# Sub_B_PCB.net
KiCad netlist of a schematic drawn in Altium Designer
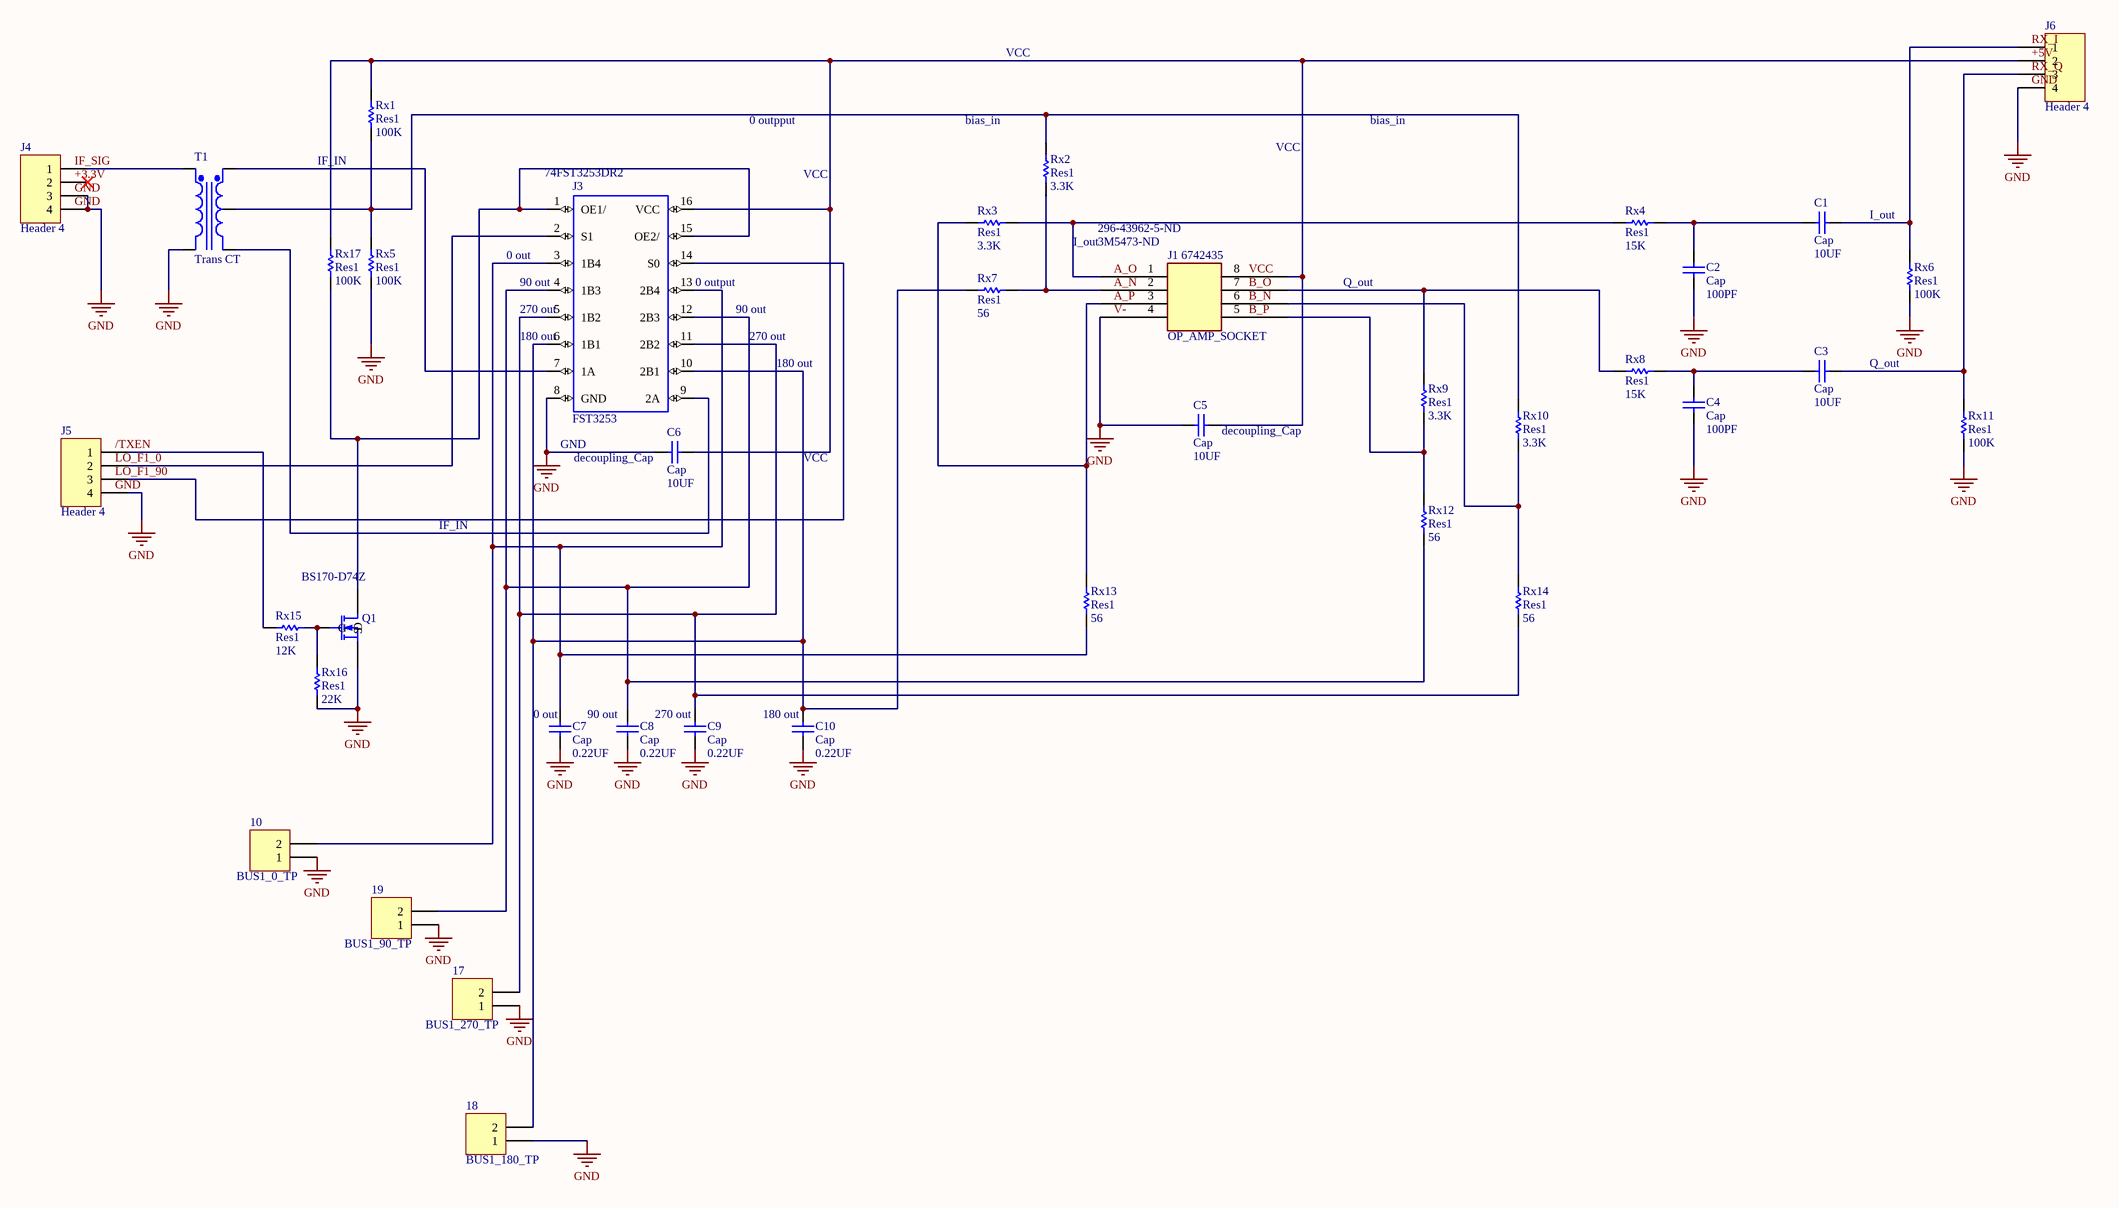
[diagram p0: Sub_B_PCB.SchDoc]

(export (version "E")
  (design (tool "Eeschema 10.0.6"))
  (components
    (comp (ref "10")
      (value "BUS1_0_TP")
      (footprint "HDR1X2")
      (description "Header, 2-Pin")
      (fields (field (name "PUBLISHER") "Altium Limited"))
      (libsource (lib "Miscellaneous Connectors") (part "Header 2"))
    )
    (comp (ref "17")
      (value "BUS1_270_TP")
      (footprint "HDR1X2")
      (description "Header, 2-Pin")
      (fields (field (name "PUBLISHER") "Altium Limited"))
      (libsource (lib "Miscellaneous Connectors") (part "Header 2"))
    )
    (comp (ref "18")
      (value "BUS1_180_TP")
      (footprint "HDR1X2")
      (description "Header, 2-Pin")
      (fields (field (name "PUBLISHER") "Altium Limited"))
      (libsource (lib "Miscellaneous Connectors") (part "Header 2"))
    )
    (comp (ref "19")
      (value "BUS1_90_TP")
      (footprint "HDR1X2")
      (description "Header, 2-Pin")
      (fields (field (name "PUBLISHER") "Altium Limited"))
      (libsource (lib "Miscellaneous Connectors") (part "Header 2"))
    )
    (comp (ref "C1")
      (value "Cap")
      (footprint "1206")
      (description "Capacitor")
      (fields
        (field (name "ALTIUM_VALUE") "10UF")
        (field (name "MANUFACTURER PART NUMBER") "885012108017")
        (field (name "PUBLISHER") "Altium Limited")
      )
      (libsource (lib "ECE295-Capacitors-SMT") (part "CAP CER 10UF 16V X5R 1206"))
    )
    (comp (ref "C2")
      (value "Cap")
      (footprint "RADIAL-0.1")
      (description "Capacitor")
      (fields
        (field (name "ALTIUM_VALUE") "100PF")
        (field (name "MANUFACTURER PART NUMBER") "K101K15C0GF53L2")
        (field (name "PUBLISHER") "Altium Limited")
      )
      (libsource (lib "ECE295-Capacitors-TH") (part "CAP CER 100PF 50V C0G/NP0 RADIAL"))
    )
    (comp (ref "C3")
      (value "Cap")
      (footprint "1206")
      (description "Capacitor")
      (fields
        (field (name "ALTIUM_VALUE") "10UF")
        (field (name "MANUFACTURER PART NUMBER") "885012108017")
        (field (name "PUBLISHER") "Altium Limited")
      )
      (libsource (lib "ECE295-Capacitors-SMT") (part "CAP CER 10UF 16V X5R 1206"))
    )
    (comp (ref "C4")
      (value "Cap")
      (footprint "RADIAL-0.1")
      (description "Capacitor")
      (fields
        (field (name "ALTIUM_VALUE") "100PF")
        (field (name "MANUFACTURER PART NUMBER") "K101K15C0GF53L2")
        (field (name "PUBLISHER") "Altium Limited")
      )
      (libsource (lib "ECE295-Capacitors-TH") (part "CAP CER 100PF 50V C0G/NP0 RADIAL"))
    )
    (comp (ref "C5")
      (value "Cap")
      (footprint "1206")
      (description "Capacitor")
      (fields
        (field (name "ALTIUM_VALUE") "10UF")
        (field (name "MANUFACTURER PART NUMBER") "885012108017")
        (field (name "PUBLISHER") "Altium Limited")
      )
      (libsource (lib "ECE295-Capacitors-SMT") (part "CAP CER 10UF 16V X5R 1206"))
    )
    (comp (ref "C6")
      (value "Cap")
      (footprint "1206")
      (description "Capacitor")
      (fields
        (field (name "ALTIUM_VALUE") "10UF")
        (field (name "MANUFACTURER PART NUMBER") "885012108017")
        (field (name "PUBLISHER") "Altium Limited")
      )
      (libsource (lib "ECE295-Capacitors-SMT") (part "CAP CER 10UF 16V X5R 1206"))
    )
    (comp (ref "C7")
      (value "Cap")
      (footprint "RADIAL-0.1")
      (description "Capacitor")
      (fields
        (field (name "ALTIUM_VALUE") "0.22UF")
        (field (name "MANUFACTURER PART NUMBER") "C320C224M5U5TA")
        (field (name "PUBLISHER") "Altium Limited")
      )
      (libsource (lib "ECE295-Capacitors-TH") (part "CAP CER 0.22UF 50V Z5U RADIAL"))
    )
    (comp (ref "C8")
      (value "Cap")
      (footprint "RADIAL-0.1")
      (description "Capacitor")
      (fields
        (field (name "ALTIUM_VALUE") "0.22UF")
        (field (name "MANUFACTURER PART NUMBER") "C320C224M5U5TA")
        (field (name "PUBLISHER") "Altium Limited")
      )
      (libsource (lib "ECE295-Capacitors-TH") (part "CAP CER 0.22UF 50V Z5U RADIAL"))
    )
    (comp (ref "C9")
      (value "Cap")
      (footprint "RADIAL-0.1")
      (description "Capacitor")
      (fields
        (field (name "ALTIUM_VALUE") "0.22UF")
        (field (name "MANUFACTURER PART NUMBER") "C320C224M5U5TA")
        (field (name "PUBLISHER") "Altium Limited")
      )
      (libsource (lib "ECE295-Capacitors-TH") (part "CAP CER 0.22UF 50V Z5U RADIAL"))
    )
    (comp (ref "C10")
      (value "Cap")
      (footprint "RADIAL-0.1")
      (description "Capacitor")
      (fields
        (field (name "ALTIUM_VALUE") "0.22UF")
        (field (name "MANUFACTURER PART NUMBER") "C320C224M5U5TA")
        (field (name "PUBLISHER") "Altium Limited")
      )
      (libsource (lib "ECE295-Capacitors-TH") (part "CAP CER 0.22UF 50V Z5U RADIAL"))
    )
    (comp (ref "J1")
      (value "OP_AMP_SOCKET")
      (footprint "TE_1-2199298-2")
      (description "8 _2 x 4_ Pos DIP, 0.3 _7.62mm_ Row Spacing Socket Tin Through Hole")
      (fields
        (field (name "MF") "TE Connectivity")
        (field (name "MP") "1-2199298-2")
        (field (name "SUPPLIER PART NUMBER 2") "6742435")
        (field (name "SUPPLIER PART NUMBER 3") "3M5473-ND")
        (field (name "SUPPLIER PART NUMBER 4") "296-43962-5-ND")
      )
      (libsource (lib "1-2199298-2") (part "1-2199298-2"))
    )
    (comp (ref "J3")
      (value "FST3253")
      (footprint "SOIC127P600X175-16N")
      (description "Multiplekser/demultiplekser 2 x 4:1 16-TSSOP")
      (fields (field (name "MF") "ON Semiconductor") (field (name "SUPPLIER PART NUMBER 1") "74FST3253DR2"))
      (libsource (lib "FST3253") (part "FST3253"))
    )
    (comp (ref "J4")
      (value "Header 4")
      (footprint "HDR1X4")
      (description "Header, 4-Pin")
      (fields (field (name "PUBLISHER") "Altium Limited"))
      (libsource (lib "") (part "Header 4_1"))
    )
    (comp (ref "J5")
      (value "Header 4")
      (footprint "HDR1X4")
      (description "Header, 4-Pin")
      (fields (field (name "PUBLISHER") "Altium Limited"))
      (libsource (lib "") (part "Header 4_1"))
    )
    (comp (ref "J6")
      (value "Header 4")
      (footprint "HDR1X4")
      (description "Header, 4-Pin")
      (fields (field (name "PUBLISHER") "Altium Limited"))
      (libsource (lib "Miscellaneous Connectors") (part "Header 4"))
    )
    (comp (ref "Q1")
      (value "MOSFET-N")
      (footprint "E3")
      (description "N-Channel MOSFET")
      (fields
        (field (name "SUPPLIER PART NUMBER 1") "BS170-D74Z")
        (field (name "PUBLISHER") "Altium Limited")
      )
      (libsource (lib "Miscellaneous Devices") (part "MOSFET-N"))
    )
    (comp (ref "Rx1")
      (value "Res1")
      (footprint "AXIAL-0.1-RES")
      (description "Resistor")
      (fields
        (field (name "ALTIUM_VALUE") "100K")
        (field (name "MANUFACTURER PART NUMBER") "CFR-25JB-52-100K")
        (field (name "TOLERANCE") "0.05")
        (field (name "PUBLISHER") "Altium Limited")
      )
      (libsource (lib "ECE295-Resistors-TH") (part "RES 100K OHM 5% 1/4W AXIAL"))
    )
    (comp (ref "Rx2")
      (value "Res1")
      (footprint "AXIAL-0.1-RES")
      (description "Resistor")
      (fields
        (field (name "ALTIUM_VALUE") "3.3K")
        (field (name "MANUFACTURER PART NUMBER") "CFR-25JB-52-3K3")
        (field (name "TOLERANCE") "0.05")
        (field (name "PUBLISHER") "Altium Limited")
      )
      (libsource (lib "ECE295-Resistors-TH") (part "RES 3.3K OHM 5% 1/4W AXIAL"))
    )
    (comp (ref "Rx3")
      (value "Res1")
      (footprint "AXIAL-0.1-RES")
      (description "Resistor")
      (fields
        (field (name "ALTIUM_VALUE") "3.3K")
        (field (name "MANUFACTURER PART NUMBER") "CFR-25JB-52-3K3")
        (field (name "TOLERANCE") "0.05")
        (field (name "PUBLISHER") "Altium Limited")
      )
      (libsource (lib "ECE295-Resistors-TH") (part "RES 3.3K OHM 5% 1/4W AXIAL"))
    )
    (comp (ref "Rx4")
      (value "Res1")
      (footprint "AXIAL-0.1-RES")
      (description "Resistor")
      (fields
        (field (name "ALTIUM_VALUE") "15K")
        (field (name "MANUFACTURER PART NUMBER") "CFR-25JB-52-15K")
        (field (name "TOLERANCE") "0.05")
        (field (name "PUBLISHER") "Altium Limited")
      )
      (libsource (lib "ECE295-Resistors-TH") (part "RES 15K OHM 5% 1/4W AXIAL"))
    )
    (comp (ref "Rx5")
      (value "Res1")
      (footprint "AXIAL-0.1-RES")
      (description "Resistor")
      (fields
        (field (name "ALTIUM_VALUE") "100K")
        (field (name "MANUFACTURER PART NUMBER") "CFR-25JB-52-100K")
        (field (name "TOLERANCE") "0.05")
        (field (name "PUBLISHER") "Altium Limited")
      )
      (libsource (lib "ECE295-Resistors-TH") (part "RES 100K OHM 5% 1/4W AXIAL"))
    )
    (comp (ref "Rx6")
      (value "Res1")
      (footprint "AXIAL-0.1-RES")
      (description "Resistor")
      (fields
        (field (name "ALTIUM_VALUE") "100K")
        (field (name "MANUFACTURER PART NUMBER") "CFR-25JB-52-100K")
        (field (name "TOLERANCE") "0.05")
        (field (name "PUBLISHER") "Altium Limited")
      )
      (libsource (lib "ECE295-Resistors-TH") (part "RES 100K OHM 5% 1/4W AXIAL"))
    )
    (comp (ref "Rx7")
      (value "Res1")
      (footprint "AXIAL-0.1-RES")
      (description "Resistor")
      (fields
        (field (name "ALTIUM_VALUE") "56")
        (field (name "MANUFACTURER PART NUMBER") "CFR-25JB-52-56R")
        (field (name "TOLERANCE") "0.05")
        (field (name "PUBLISHER") "Altium Limited")
      )
      (libsource (lib "ECE295-Resistors-TH") (part "RES 56 OHM 5% 1/4W AXIAL"))
    )
    (comp (ref "Rx8")
      (value "Res1")
      (footprint "AXIAL-0.1-RES")
      (description "Resistor")
      (fields
        (field (name "ALTIUM_VALUE") "15K")
        (field (name "MANUFACTURER PART NUMBER") "CFR-25JB-52-15K")
        (field (name "TOLERANCE") "0.05")
        (field (name "PUBLISHER") "Altium Limited")
      )
      (libsource (lib "ECE295-Resistors-TH") (part "RES 15K OHM 5% 1/4W AXIAL"))
    )
    (comp (ref "Rx9")
      (value "Res1")
      (footprint "AXIAL-0.1-RES")
      (description "Resistor")
      (fields
        (field (name "ALTIUM_VALUE") "3.3K")
        (field (name "MANUFACTURER PART NUMBER") "CFR-25JB-52-3K3")
        (field (name "TOLERANCE") "0.05")
        (field (name "PUBLISHER") "Altium Limited")
      )
      (libsource (lib "ECE295-Resistors-TH") (part "RES 3.3K OHM 5% 1/4W AXIAL"))
    )
    (comp (ref "Rx10")
      (value "Res1")
      (footprint "AXIAL-0.1-RES")
      (description "Resistor")
      (fields
        (field (name "ALTIUM_VALUE") "3.3K")
        (field (name "MANUFACTURER PART NUMBER") "CFR-25JB-52-3K3")
        (field (name "TOLERANCE") "0.05")
        (field (name "PUBLISHER") "Altium Limited")
      )
      (libsource (lib "ECE295-Resistors-TH") (part "RES 3.3K OHM 5% 1/4W AXIAL"))
    )
    (comp (ref "Rx11")
      (value "Res1")
      (footprint "AXIAL-0.1-RES")
      (description "Resistor")
      (fields
        (field (name "ALTIUM_VALUE") "100K")
        (field (name "MANUFACTURER PART NUMBER") "CFR-25JB-52-100K")
        (field (name "TOLERANCE") "0.05")
        (field (name "PUBLISHER") "Altium Limited")
      )
      (libsource (lib "ECE295-Resistors-TH") (part "RES 100K OHM 5% 1/4W AXIAL"))
    )
    (comp (ref "Rx12")
      (value "Res1")
      (footprint "AXIAL-0.1-RES")
      (description "Resistor")
      (fields
        (field (name "ALTIUM_VALUE") "56")
        (field (name "MANUFACTURER PART NUMBER") "CFR-25JB-52-56R")
        (field (name "TOLERANCE") "0.05")
        (field (name "PUBLISHER") "Altium Limited")
      )
      (libsource (lib "ECE295-Resistors-TH") (part "RES 56 OHM 5% 1/4W AXIAL"))
    )
    (comp (ref "Rx13")
      (value "Res1")
      (footprint "AXIAL-0.1-RES")
      (description "Resistor")
      (fields
        (field (name "ALTIUM_VALUE") "56")
        (field (name "MANUFACTURER PART NUMBER") "CFR-25JB-52-56R")
        (field (name "TOLERANCE") "0.05")
        (field (name "PUBLISHER") "Altium Limited")
      )
      (libsource (lib "ECE295-Resistors-TH") (part "RES 56 OHM 5% 1/4W AXIAL"))
    )
    (comp (ref "Rx14")
      (value "Res1")
      (footprint "AXIAL-0.1-RES")
      (description "Resistor")
      (fields
        (field (name "ALTIUM_VALUE") "56")
        (field (name "MANUFACTURER PART NUMBER") "CFR-25JB-52-56R")
        (field (name "TOLERANCE") "0.05")
        (field (name "PUBLISHER") "Altium Limited")
      )
      (libsource (lib "ECE295-Resistors-TH") (part "RES 56 OHM 5% 1/4W AXIAL"))
    )
    (comp (ref "Rx15")
      (value "Res1")
      (footprint "AXIAL-0.1-RES")
      (description "Resistor")
      (fields
        (field (name "ALTIUM_VALUE") "12K")
        (field (name "MANUFACTURER PART NUMBER") "CFR-25JB-52-12K")
        (field (name "TOLERANCE") "0.05")
        (field (name "PUBLISHER") "Altium Limited")
      )
      (libsource (lib "ECE295-Resistors-TH") (part "RES 12K OHM 5% 1/4W AXIAL"))
    )
    (comp (ref "Rx16")
      (value "Res1")
      (footprint "AXIAL-0.1-RES")
      (description "Resistor")
      (fields
        (field (name "ALTIUM_VALUE") "22K")
        (field (name "MANUFACTURER PART NUMBER") "CFR-25JB-52-22K")
        (field (name "TOLERANCE") "0.05")
        (field (name "PUBLISHER") "Altium Limited")
      )
      (libsource (lib "ECE295-Resistors-TH") (part "RES 22K OHM 5% 1/4W AXIAL"))
    )
    (comp (ref "Rx17")
      (value "Res1")
      (footprint "AXIAL-0.1-RES")
      (description "Resistor")
      (fields
        (field (name "ALTIUM_VALUE") "100K")
        (field (name "MANUFACTURER PART NUMBER") "CFR-25JB-52-100K")
        (field (name "TOLERANCE") "0.05")
        (field (name "PUBLISHER") "Altium Limited")
      )
      (libsource (lib "ECE295-Resistors-TH") (part "RES 100K OHM 5% 1/4W AXIAL"))
    )
    (comp (ref "T1")
      (value "Trans CT")
      (footprint "BIFILAR-2402")
      (description "Center-Tapped Transformer (Coupled Inductor Model)")
      (fields (field (name "PUBLISHER") "Altium Limited"))
      (libsource (lib "ECE295-Other") (part "Centre-tapped transformer wound on a binocular core"))
    )
  )
  (nets
    (net (code "17") (name "GND") (class "Default")
      (node (ref "10") (pin "1") (pinfunction "1_1") (pintype "passive"))
      (node (ref "17") (pin "1") (pinfunction "1_1") (pintype "passive"))
      (node (ref "18") (pin "1") (pinfunction "1_1") (pintype "passive"))
      (node (ref "19") (pin "1") (pinfunction "1_1") (pintype "passive"))
      (node (ref "C10") (pin "1") (pinfunction "1_1") (pintype "passive"))
      (node (ref "C2") (pin "1") (pinfunction "1_1") (pintype "passive"))
      (node (ref "C4") (pin "1") (pinfunction "1_1") (pintype "passive"))
      (node (ref "C5") (pin "1") (pinfunction "1_1") (pintype "passive"))
      (node (ref "C6") (pin "1") (pinfunction "1_1") (pintype "passive"))
      (node (ref "C7") (pin "1") (pinfunction "1_1") (pintype "passive"))
      (node (ref "C8") (pin "1") (pinfunction "1_1") (pintype "passive"))
      (node (ref "C9") (pin "1") (pinfunction "1_1") (pintype "passive"))
      (node (ref "J1") (pin "4") (pinfunction "V-_4") (pintype "passive"))
      (node (ref "J3") (pin "8") (pinfunction "GND_8") (pintype "bidirectional"))
      (node (ref "J4") (pin "3") (pinfunction "3_3") (pintype "passive"))
      (node (ref "J4") (pin "4") (pinfunction "4_4") (pintype "passive"))
      (node (ref "J5") (pin "4") (pinfunction "4_4") (pintype "passive"))
      (node (ref "J6") (pin "4") (pinfunction "4_4") (pintype "passive"))
      (node (ref "Q1") (pin "3") (pinfunction "S_3") (pintype "passive"))
      (node (ref "Rx11") (pin "1") (pinfunction "1_1") (pintype "passive"))
      (node (ref "Rx16") (pin "1") (pinfunction "1_1") (pintype "passive"))
      (node (ref "Rx5") (pin "1") (pinfunction "1_1") (pintype "passive"))
      (node (ref "Rx6") (pin "1") (pinfunction "1_1") (pintype "passive"))
      (node (ref "T1") (pin "5") (pinfunction "Pri-_5") (pintype "passive"))
    )
    (net (code "18") (name "Net-(C1-Pad1)") (class "Default")
      (node (ref "C1") (pin "1") (pinfunction "1_1") (pintype "passive"))
      (node (ref "C2") (pin "2") (pinfunction "2_2") (pintype "passive"))
      (node (ref "Rx4") (pin "2") (pinfunction "2_2") (pintype "passive"))
    )
    (net (code "19") (name "Net-(C1-Pad2)") (class "Default")
      (node (ref "C1") (pin "2") (pinfunction "2_2") (pintype "passive"))
      (node (ref "J6") (pin "1") (pinfunction "1_1") (pintype "passive"))
      (node (ref "Rx6") (pin "2") (pinfunction "2_2") (pintype "passive"))
    )
    (net (code "20") (name "Net-(C3-Pad1)") (class "Default")
      (node (ref "C3") (pin "1") (pinfunction "1_1") (pintype "passive"))
      (node (ref "C4") (pin "2") (pinfunction "2_2") (pintype "passive"))
      (node (ref "Rx8") (pin "2") (pinfunction "2_2") (pintype "passive"))
    )
    (net (code "21") (name "Net-(C3-Pad2)") (class "Default")
      (node (ref "C3") (pin "2") (pinfunction "2_2") (pintype "passive"))
      (node (ref "J6") (pin "3") (pinfunction "3_3") (pintype "passive"))
      (node (ref "Rx11") (pin "2") (pinfunction "2_2") (pintype "passive"))
    )
    (net (code "22") (name "Net-(J1-INVERTING_A)") (class "Default")
      (node (ref "J1") (pin "2") (pinfunction "INVERTING_A_2") (pintype "passive"))
      (node (ref "Rx2") (pin "1") (pinfunction "1_1") (pintype "passive"))
      (node (ref "Rx7") (pin "2") (pinfunction "2_2") (pintype "passive"))
    )
    (net (code "23") (name "Net-(J1-INVERTING_B)") (class "Default")
      (node (ref "J1") (pin "6") (pinfunction "INVERTING_B_6") (pintype "passive"))
      (node (ref "Rx10") (pin "1") (pinfunction "1_1") (pintype "passive"))
      (node (ref "Rx14") (pin "2") (pinfunction "2_2") (pintype "passive"))
    )
    (net (code "24") (name "Net-(J1-NON-INVERTING_A)") (class "Default")
      (node (ref "J1") (pin "3") (pinfunction "NON-INVERTING_A_3") (pintype "passive"))
      (node (ref "Rx13") (pin "2") (pinfunction "2_2") (pintype "passive"))
      (node (ref "Rx3") (pin "1") (pinfunction "1_1") (pintype "passive"))
    )
    (net (code "25") (name "Net-(J1-NON-INVERTING_B)") (class "Default")
      (node (ref "J1") (pin "5") (pinfunction "NON-INVERTING_B_5") (pintype "passive"))
      (node (ref "Rx12") (pin "2") (pinfunction "2_2") (pintype "passive"))
      (node (ref "Rx9") (pin "1") (pinfunction "1_1") (pintype "passive"))
    )
    (net (code "26") (name "Net-(J1-OOUTPUT__A)") (class "Default")
      (node (ref "J1") (pin "1") (pinfunction "OOUTPUT__A_1") (pintype "passive"))
      (node (ref "Rx3") (pin "2") (pinfunction "2_2") (pintype "passive"))
      (node (ref "Rx4") (pin "1") (pinfunction "1_1") (pintype "passive"))
    )
    (net (code "27") (name "Net-(J1-OUTPUT_B)") (class "Default")
      (node (ref "J1") (pin "7") (pinfunction "OUTPUT_B_7") (pintype "passive"))
      (node (ref "Rx8") (pin "1") (pinfunction "1_1") (pintype "passive"))
      (node (ref "Rx9") (pin "2") (pinfunction "2_2") (pintype "passive"))
    )
    (net (code "28") (name "Net-(J1-VCC)") (class "Default")
      (node (ref "C5") (pin "2") (pinfunction "2_2") (pintype "passive"))
      (node (ref "C6") (pin "2") (pinfunction "2_2") (pintype "passive"))
      (node (ref "J1") (pin "8") (pinfunction "VCC_8") (pintype "passive"))
      (node (ref "J3") (pin "16") (pinfunction "VCC_16") (pintype "bidirectional"))
      (node (ref "J6") (pin "2") (pinfunction "2_2") (pintype "passive"))
      (node (ref "Rx1") (pin "2") (pinfunction "2_2") (pintype "passive"))
      (node (ref "Rx17") (pin "2") (pinfunction "2_2") (pintype "passive"))
    )
    (net (code "29") (name "Net-(J3-1A)") (class "Default")
      (node (ref "J3") (pin "7") (pinfunction "1A_7") (pintype "bidirectional"))
      (node (ref "T1") (pin "1") (pinfunction "Sec+_1") (pintype "passive"))
    )
    (net (code "30") (name "Net-(J3-1B1)") (class "Default")
      (node (ref "18") (pin "2") (pinfunction "2_2") (pintype "passive"))
      (node (ref "C10") (pin "2") (pinfunction "2_2") (pintype "passive"))
      (node (ref "J3") (pin "10") (pinfunction "2B1_10") (pintype "bidirectional"))
      (node (ref "J3") (pin "6") (pinfunction "1B1_6") (pintype "bidirectional"))
      (node (ref "Rx7") (pin "1") (pinfunction "1_1") (pintype "passive"))
    )
    (net (code "31") (name "Net-(J3-1B2)") (class "Default")
      (node (ref "17") (pin "2") (pinfunction "2_2") (pintype "passive"))
      (node (ref "C9") (pin "2") (pinfunction "2_2") (pintype "passive"))
      (node (ref "J3") (pin "11") (pinfunction "2B2_11") (pintype "bidirectional"))
      (node (ref "J3") (pin "5") (pinfunction "1B2_5") (pintype "bidirectional"))
      (node (ref "Rx14") (pin "1") (pinfunction "1_1") (pintype "passive"))
    )
    (net (code "32") (name "Net-(J3-1B3)") (class "Default")
      (node (ref "19") (pin "2") (pinfunction "2_2") (pintype "passive"))
      (node (ref "C8") (pin "2") (pinfunction "2_2") (pintype "passive"))
      (node (ref "J3") (pin "12") (pinfunction "2B3_12") (pintype "bidirectional"))
      (node (ref "J3") (pin "4") (pinfunction "1B3_4") (pintype "bidirectional"))
      (node (ref "Rx12") (pin "1") (pinfunction "1_1") (pintype "passive"))
    )
    (net (code "33") (name "Net-(J3-1B4)") (class "Default")
      (node (ref "10") (pin "2") (pinfunction "2_2") (pintype "passive"))
      (node (ref "C7") (pin "2") (pinfunction "2_2") (pintype "passive"))
      (node (ref "J3") (pin "13") (pinfunction "2B4_13") (pintype "bidirectional"))
      (node (ref "J3") (pin "3") (pinfunction "1B4_3") (pintype "bidirectional"))
      (node (ref "Rx13") (pin "1") (pinfunction "1_1") (pintype "passive"))
    )
    (net (code "34") (name "Net-(J3-2A)") (class "Default")
      (node (ref "J3") (pin "9") (pinfunction "2A_9") (pintype "bidirectional"))
      (node (ref "T1") (pin "3") (pinfunction "Sec-_3") (pintype "passive"))
    )
    (net (code "35") (name "Net-(J3-OE1{slash})") (class "Default")
      (node (ref "J3") (pin "1") (pinfunction "OE1/_1") (pintype "bidirectional"))
      (node (ref "J3") (pin "15") (pinfunction "OE2/_15") (pintype "bidirectional"))
      (node (ref "Q1") (pin "1") (pinfunction "D_1") (pintype "passive"))
      (node (ref "Rx17") (pin "1") (pinfunction "1_1") (pintype "passive"))
    )
    (net (code "36") (name "Net-(J3-S0)") (class "Default")
      (node (ref "J3") (pin "14") (pinfunction "S0_14") (pintype "bidirectional"))
      (node (ref "J5") (pin "3") (pinfunction "3_3") (pintype "passive"))
    )
    (net (code "37") (name "Net-(J3-S1)") (class "Default")
      (node (ref "J3") (pin "2") (pinfunction "S1_2") (pintype "bidirectional"))
      (node (ref "J5") (pin "2") (pinfunction "2_2") (pintype "passive"))
    )
    (net (code "38") (name "Net-(J5-Pad1)") (class "Default")
      (node (ref "J5") (pin "1") (pinfunction "1_1") (pintype "passive"))
      (node (ref "Rx15") (pin "1") (pinfunction "1_1") (pintype "passive"))
    )
    (net (code "39") (name "Net-(Q1-G)") (class "Default")
      (node (ref "Q1") (pin "2") (pinfunction "G_2") (pintype "passive"))
      (node (ref "Rx15") (pin "2") (pinfunction "2_2") (pintype "passive"))
      (node (ref "Rx16") (pin "2") (pinfunction "2_2") (pintype "passive"))
    )
    (net (code "40") (name "Net-(T1-Pri+)") (class "Default")
      (node (ref "J4") (pin "1") (pinfunction "1_1") (pintype "passive"))
      (node (ref "T1") (pin "4") (pinfunction "Pri+_4") (pintype "passive"))
    )
    (net (code "41") (name "Net-(T1-SecCT)") (class "Default")
      (node (ref "Rx1") (pin "1") (pinfunction "1_1") (pintype "passive"))
      (node (ref "Rx10") (pin "2") (pinfunction "2_2") (pintype "passive"))
      (node (ref "Rx2") (pin "2") (pinfunction "2_2") (pintype "passive"))
      (node (ref "Rx5") (pin "2") (pinfunction "2_2") (pintype "passive"))
      (node (ref "T1") (pin "2") (pinfunction "SecCT_2") (pintype "passive"))
    )
    (net (code "42") (name "unconnected-(J4-Pad2)") (class "Default")
      (node (ref "J4") (pin "2") (pinfunction "2_2") (pintype "passive+no_connect"))
    )
  )
)
